# SNES_RGBAmp.net
KiCad netlist of a schematic drawn in EAGLE
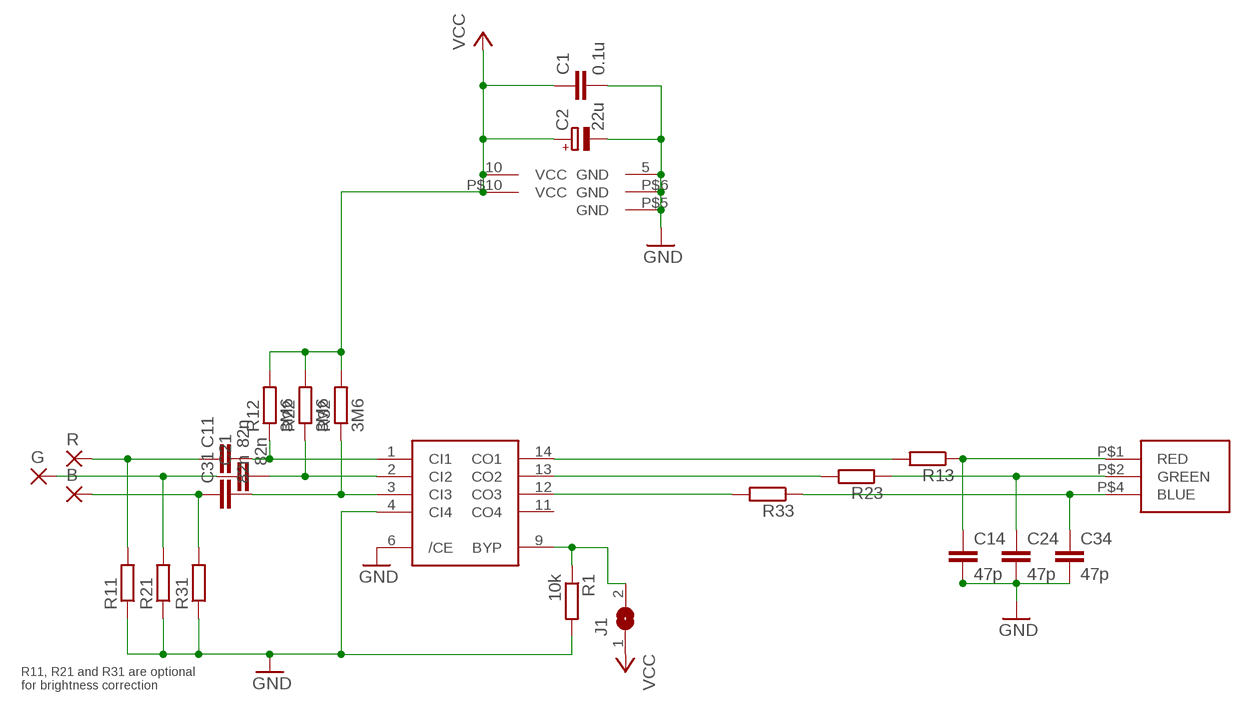
[diagram p0: schematic, sheet 1]

(export (version "E")
  (design (tool "Eeschema 10.0.6"))
  (components
    (comp (ref "B")
      (value "SMD2")
      (footprint "eagle-import:SMD1,27-2,54")
      (libsource (lib "eagle-import") (part "SMD2"))
    )
    (comp (ref "C1")
      (value "0.1u")
      (footprint "eagle-import:C0603K")
      (libsource (lib "eagle-import") (part "C-EUC0603K"))
    )
    (comp (ref "C2")
      (value "22u")
      (footprint "eagle-import:SMC_B")
      (libsource (lib "eagle-import") (part "CPOL-EUSMCB"))
    )
    (comp (ref "C11")
      (value "82n")
      (footprint "eagle-import:C0603K")
      (libsource (lib "eagle-import") (part "C-EUC0603K"))
    )
    (comp (ref "C14")
      (value "47p")
      (footprint "eagle-import:C0603K")
      (libsource (lib "eagle-import") (part "C-EUC0603K"))
    )
    (comp (ref "C21")
      (value "82n")
      (footprint "eagle-import:C0603K")
      (libsource (lib "eagle-import") (part "C-EUC0603K"))
    )
    (comp (ref "C24")
      (value "47p")
      (footprint "eagle-import:C0603K")
      (libsource (lib "eagle-import") (part "C-EUC0603K"))
    )
    (comp (ref "C31")
      (value "82n")
      (footprint "eagle-import:C0603K")
      (libsource (lib "eagle-import") (part "C-EUC0603K"))
    )
    (comp (ref "C34")
      (value "47p")
      (footprint "eagle-import:C0603K")
      (libsource (lib "eagle-import") (part "C-EUC0603K"))
    )
    (comp (ref "G")
      (value "SMD2")
      (footprint "eagle-import:SMD1,27-2,54")
      (libsource (lib "eagle-import") (part "SMD2"))
    )
    (comp (ref "J1") (value "SJ") (footprint "eagle-import:SJ") (libsource (lib "eagle-import") (part "SJ")))
    (comp (ref "R")
      (value "SMD2")
      (footprint "eagle-import:SMD1,27-2,54")
      (libsource (lib "eagle-import") (part "SMD2"))
    )
    (comp (ref "R1")
      (value "10k")
      (footprint "eagle-import:R0603")
      (libsource (lib "eagle-import") (part "R-EU_R0603"))
    )
    (comp (ref "R11")
      (value "R-EU_R0603")
      (footprint "eagle-import:R0603")
      (libsource (lib "eagle-import") (part "R-EU_R0603"))
    )
    (comp (ref "R12")
      (value "3M6")
      (footprint "eagle-import:R0603")
      (libsource (lib "eagle-import") (part "R-EU_R0603"))
    )
    (comp (ref "R13")
      (value "R-EU_R0603")
      (footprint "eagle-import:R0603")
      (libsource (lib "eagle-import") (part "R-EU_R0603"))
    )
    (comp (ref "R21")
      (value "R-EU_R0603")
      (footprint "eagle-import:R0603")
      (libsource (lib "eagle-import") (part "R-EU_R0603"))
    )
    (comp (ref "R22")
      (value "3M6")
      (footprint "eagle-import:R0603")
      (libsource (lib "eagle-import") (part "R-EU_R0603"))
    )
    (comp (ref "R23")
      (value "R-EU_R0603")
      (footprint "eagle-import:R0603")
      (libsource (lib "eagle-import") (part "R-EU_R0603"))
    )
    (comp (ref "R31")
      (value "R-EU_R0603")
      (footprint "eagle-import:R0603")
      (libsource (lib "eagle-import") (part "R-EU_R0603"))
    )
    (comp (ref "R32")
      (value "3M6")
      (footprint "eagle-import:R0603")
      (libsource (lib "eagle-import") (part "R-EU_R0603"))
    )
    (comp (ref "R33")
      (value "R-EU_R0603")
      (footprint "eagle-import:R0603")
      (libsource (lib "eagle-import") (part "R-EU_R0603"))
    )
    (comp (ref "U$1")
      (value "SNES_MULTIAV_RGB_ONLY")
      (footprint "eagle-import:SNES_MULTIAV_RGB_ONLY")
      (libsource (lib "eagle-import") (part "SNES_MULTIAV_RGB_ONLY"))
    )
    (comp (ref "U1")
      (value "THS7374")
      (footprint "eagle-import:THS7374")
      (libsource (lib "eagle-import") (part "THS7374"))
    )
  )
  (nets
    (net (code "1") (name "GND") (class "Default")
      (node (ref "C1") (pin "2") (pinfunction "2_2") (pintype "passive"))
      (node (ref "C14") (pin "2") (pinfunction "2_2") (pintype "passive"))
      (node (ref "C2") (pin "-") (pinfunction "-_-") (pintype "passive"))
      (node (ref "C24") (pin "2") (pinfunction "2_2") (pintype "passive"))
      (node (ref "C34") (pin "2") (pinfunction "2_2") (pintype "passive"))
      (node (ref "R1") (pin "2") (pinfunction "2_2") (pintype "passive"))
      (node (ref "R11") (pin "1") (pinfunction "1_1") (pintype "passive"))
      (node (ref "R21") (pin "1") (pinfunction "1_1") (pintype "passive"))
      (node (ref "R31") (pin "1") (pinfunction "1_1") (pintype "passive"))
      (node (ref "U$1") (pin "P$5") (pinfunction "GND_P$5") (pintype "bidirectional"))
      (node (ref "U$1") (pin "P$6") (pinfunction "GND_P$6") (pintype "bidirectional"))
      (node (ref "U1") (pin "4") (pinfunction "CI4_4") (pintype "bidirectional"))
      (node (ref "U1") (pin "5") (pinfunction "GND_5") (pintype "bidirectional"))
      (node (ref "U1") (pin "6") (pinfunction "/CE_6") (pintype "bidirectional"))
    )
    (net (code "2") (name "Net-(B-P)") (class "Default")
      (node (ref "B") (pin "1") (pinfunction "P_1") (pintype "passive"))
      (node (ref "C31") (pin "1") (pinfunction "1_1") (pintype "passive"))
      (node (ref "R31") (pin "2") (pinfunction "2_2") (pintype "passive"))
    )
    (net (code "3") (name "Net-(G-P)") (class "Default")
      (node (ref "C21") (pin "1") (pinfunction "1_1") (pintype "passive"))
      (node (ref "G") (pin "1") (pinfunction "P_1") (pintype "passive"))
      (node (ref "R21") (pin "2") (pinfunction "2_2") (pintype "passive"))
    )
    (net (code "4") (name "Net-(R-P)") (class "Default")
      (node (ref "C11") (pin "1") (pinfunction "1_1") (pintype "passive"))
      (node (ref "R") (pin "1") (pinfunction "P_1") (pintype "passive"))
      (node (ref "R11") (pin "2") (pinfunction "2_2") (pintype "passive"))
    )
    (net (code "5") (name "Net-(U$1C-BLUE)") (class "Default")
      (node (ref "C34") (pin "1") (pinfunction "1_1") (pintype "passive"))
      (node (ref "R33") (pin "1") (pinfunction "1_1") (pintype "passive"))
      (node (ref "U$1") (pin "P$4") (pinfunction "BLUE_P$4") (pintype "bidirectional"))
    )
    (net (code "6") (name "Net-(U$1C-GREEN)") (class "Default")
      (node (ref "C24") (pin "1") (pinfunction "1_1") (pintype "passive"))
      (node (ref "R23") (pin "1") (pinfunction "1_1") (pintype "passive"))
      (node (ref "U$1") (pin "P$2") (pinfunction "GREEN_P$2") (pintype "bidirectional"))
    )
    (net (code "7") (name "Net-(U$1C-RED)") (class "Default")
      (node (ref "C14") (pin "1") (pinfunction "1_1") (pintype "passive"))
      (node (ref "R13") (pin "1") (pinfunction "1_1") (pintype "passive"))
      (node (ref "U$1") (pin "P$1") (pinfunction "RED_P$1") (pintype "bidirectional"))
    )
    (net (code "8") (name "Net-(U1A-BYP)") (class "Default")
      (node (ref "J1") (pin "2") (pinfunction "2_2") (pintype "passive"))
      (node (ref "R1") (pin "1") (pinfunction "1_1") (pintype "passive"))
      (node (ref "U1") (pin "9") (pinfunction "BYP_9") (pintype "bidirectional"))
    )
    (net (code "9") (name "Net-(U1A-CI1)") (class "Default")
      (node (ref "C11") (pin "2") (pinfunction "2_2") (pintype "passive"))
      (node (ref "R12") (pin "1") (pinfunction "1_1") (pintype "passive"))
      (node (ref "U1") (pin "1") (pinfunction "CI1_1") (pintype "bidirectional"))
    )
    (net (code "10") (name "Net-(U1A-CI2)") (class "Default")
      (node (ref "C21") (pin "2") (pinfunction "2_2") (pintype "passive"))
      (node (ref "R22") (pin "1") (pinfunction "1_1") (pintype "passive"))
      (node (ref "U1") (pin "2") (pinfunction "CI2_2") (pintype "bidirectional"))
    )
    (net (code "11") (name "Net-(U1A-CI3)") (class "Default")
      (node (ref "C31") (pin "2") (pinfunction "2_2") (pintype "passive"))
      (node (ref "R32") (pin "1") (pinfunction "1_1") (pintype "passive"))
      (node (ref "U1") (pin "3") (pinfunction "CI3_3") (pintype "bidirectional"))
    )
    (net (code "12") (name "Net-(U1A-CO1)") (class "Default")
      (node (ref "R13") (pin "2") (pinfunction "2_2") (pintype "passive"))
      (node (ref "U1") (pin "14") (pinfunction "CO1_14") (pintype "bidirectional"))
    )
    (net (code "13") (name "Net-(U1A-CO2)") (class "Default")
      (node (ref "R23") (pin "2") (pinfunction "2_2") (pintype "passive"))
      (node (ref "U1") (pin "13") (pinfunction "CO2_13") (pintype "bidirectional"))
    )
    (net (code "14") (name "Net-(U1A-CO3)") (class "Default")
      (node (ref "R33") (pin "2") (pinfunction "2_2") (pintype "passive"))
      (node (ref "U1") (pin "12") (pinfunction "CO3_12") (pintype "bidirectional"))
    )
    (net (code "15") (name "VCC") (class "Default")
      (node (ref "C1") (pin "1") (pinfunction "1_1") (pintype "passive"))
      (node (ref "C2") (pin "+") (pinfunction "+_+") (pintype "passive"))
      (node (ref "J1") (pin "1") (pinfunction "1_1") (pintype "passive"))
      (node (ref "R12") (pin "2") (pinfunction "2_2") (pintype "passive"))
      (node (ref "R22") (pin "2") (pinfunction "2_2") (pintype "passive"))
      (node (ref "R32") (pin "2") (pinfunction "2_2") (pintype "passive"))
      (node (ref "U$1") (pin "P$10") (pinfunction "VCC_P$10") (pintype "bidirectional"))
      (node (ref "U1") (pin "10") (pinfunction "VCC_10") (pintype "bidirectional"))
    )
    (net (code "16") (name "unconnected-(U1A-CO4-Pad11)") (class "Default")
      (node (ref "U1") (pin "11") (pinfunction "CO4_11") (pintype "bidirectional"))
    )
  )
)
